# Main.net
KiCad netlist of a schematic drawn in Altium Designer
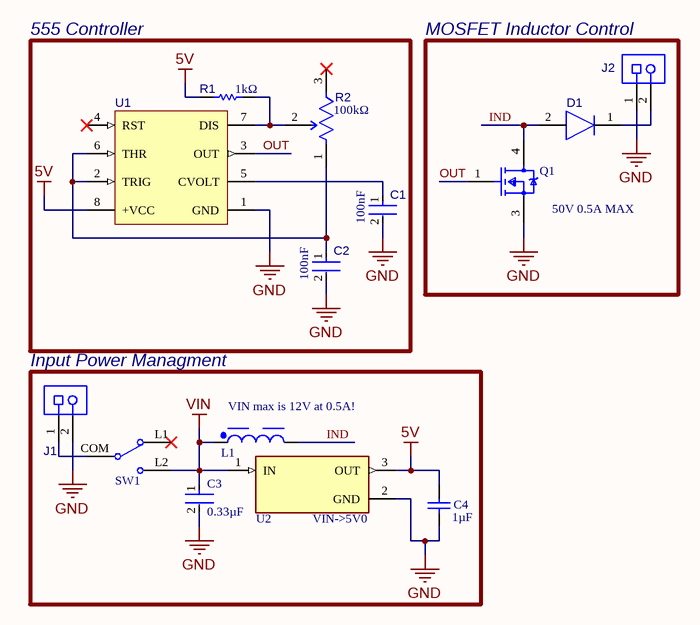
[diagram p0: Main.SchDoc]

(export (version "E")
  (design (tool "Eeschema 10.0.6"))
  (components
    (comp (ref "C1")
      (value "100nF")
      (footprint "FP-1206-L_3_2_0_2-W_1_6_0-MFG")
      (description "General Purpose Ceramic Capacitor, 1206, 100nF, 10%, X7R, 15%, 100V")
      (fields (field (name "TOLERANCE") "10%"))
      (libsource (lib "Altium Content Vault") (part "b4654b650e69147ec39a6b967a45e02"))
    )
    (comp (ref "C2")
      (value "100nF")
      (footprint "FP-1206-L_3_2_0_2-W_1_6_0-MFG")
      (description "General Purpose Ceramic Capacitor, 1206, 100nF, 10%, X7R, 15%, 100V")
      (fields (field (name "TOLERANCE") "10%"))
      (libsource (lib "Altium Content Vault") (part "b4654b650e69147ec39a6b967a45e02"))
    )
    (comp (ref "C3")
      (value "0.33µF")
      (footprint "FP-C1206C-EB-MFG")
      (description "CAP CER 0.33UF 50V X7R 1206")
      (fields
        (field (name "OCTOPART") "https://octopart.com/c1206c334k5ractu-kemet-146059")
        (field (name "MANUFACTURER PART NUMBER") "C1206C334K5RACTU")
      )
      (libsource (lib "Altium Content Vault") (part "b4654b650e69147ec39a6b967a45e02"))
    )
    (comp (ref "C4")
      (value "1µF")
      (footprint "CAPC3216X110X50LL20T25")
      (description "Chip Capacitor, 1 uF, +/- 10%, 50 V, -55 to 125 degC, 1206 (3216 Metric), RoHS, Tape and Reel")
      (fields (field (name "MANUFACTURER") "Kemet") (field (name "TOLERANCE") "10%"))
      (libsource (lib "Altium Content Vault") (part "CAP-NP-2"))
    )
    (comp (ref "D1")
      (value "S1B-13-F")
      (footprint "FP-SMA-MFG")
      (description "DIODE GEN PURP 100V 1A SMA")
      (libsource (lib "Altium Content Vault") (part "03cb15f8d8994b06d21941eb207504f"))
    )
    (comp (ref "J1")
      (value "1729128")
      (footprint "PHOE-1729128-2_V")
      (description "PCB Terminal Block, 13.5 A, 400 V, 2-Pin THD, RoHS, Bulk")
      (fields (field (name "MANUFACTURER") "Phoenix Contact"))
      (libsource (lib "Altium Content Vault") (part "CN-2P-F-R2"))
    )
    (comp (ref "J2")
      (value "1729128")
      (footprint "PHOE-1729128-2_V")
      (description "PCB Terminal Block, 13.5 A, 400 V, 2-Pin THD, RoHS, Bulk")
      (fields (field (name "MANUFACTURER") "Phoenix Contact"))
      (libsource (lib "Altium Content Vault") (part "CN-2P-F-R2"))
    )
    (comp (ref "L1")
      (value "4.7uH")
      (footprint "WE-PDA_7345")
      (description "WE-PDA SMT Shielded Power Inductor, size 7345, 4.7uH, 2.35A, 84mOhm")
      (fields
        (field (name "MANUFACTURER PART NUMBER") "784777047")
        (field (name "MANUFACTURER") "Wurth Elektronik")
      )
      (libsource (lib "Altium_WE-PDA_rev23a") (part "784777047"))
    )
    (comp (ref "Q1")
      (value "IRLZ44NSTRLPBF")
      (footprint "FP-PG-TO263-3-MFG")
      (description "MOSFET N-CH 55V 47A D2PAK")
      (libsource (lib "Altium Content Vault") (part "cdf1c68f84cb049e5ebc85739c3fcf6"))
    )
    (comp (ref "R1")
      (value "1kΩ")
      (footprint "RESC3116X65X50LL20T20")
      (fields (field (name "PART NUMBER") "CRCW12061K00JNEAHP") (field (name "MANUFACTURER") "Vishay Dale"))
      (libsource (lib "Altium Content Vault") (part "RES"))
    )
    (comp (ref "R2")
      (value "100kΩ")
      (footprint "FP-3362P-T-MFG")
      (description "TRIMMER 100K OHM 0.5W PC PIN TOP")
      (fields (field (name "TOLERANCE") "10%"))
      (libsource (lib "Altium Content Vault") (part "13357d81287629c2fd191d242cfa50c"))
    )
    (comp (ref "SW1")
      (value "450301014042")
      (footprint "450301014042")
      (description "WS-SLTV THT Mini Slide Switch, Opposite Side Connection, SPDT, 12VDC, 500mA, 800g")
      (fields (field (name "MANUFACTURER") "Wurth Elektronik"))
      (libsource (lib "Altium_WS-SLTV_rev22a") (part "450301014042"))
    )
    (comp (ref "U1")
      (value "555 Timer IC")
      (footprint "D0008A_M")
      (description "Timer, 8-pin Narrow SOIC, Pb-Free")
      (fields (field (name "MANUFACTURER") "Texas Instruments"))
      (libsource (lib "Altium Content Vault") (part "AN-TIMER-LM555-8"))
    )
    (comp (ref "U2")
      (value "VIN->5V0")
      (footprint "DPAK229P990X238-4N")
      (description "Linear Voltage Regulator IC 1 Output 1A DPAK")
      (fields (field (name "MP") "MC7805BDTRKG") (field (name "MF") "ON Semiconductor"))
      (libsource (lib "MC7805BDTRKG") (part "MC7805BDTRKG"))
    )
  )
  (nets
    (net (code "1") (name "/IND") (class "Default")
      (node (ref "D1") (pin "2") (pinfunction "A_2") (pintype "passive"))
      (node (ref "L1") (pin "2") (pinfunction "2_2") (pintype "passive"))
      (node (ref "Q1") (pin "4") (pinfunction "D_4") (pintype "passive"))
    )
    (net (code "2") (name "/OUT") (class "Default")
      (node (ref "Q1") (pin "1") (pinfunction "G_1") (pintype "passive"))
      (node (ref "U1") (pin "3") (pinfunction "OUT_3") (pintype "output"))
    )
    (net (code "3") (name "5V") (class "Default")
      (node (ref "C4") (pin "1") (pinfunction "1_1") (pintype "passive"))
      (node (ref "R1") (pin "2") (pinfunction "2_2") (pintype "passive"))
      (node (ref "U1") (pin "8") (pinfunction "+VCC_8") (pintype "power_in"))
      (node (ref "U2") (pin "3") (pinfunction "OUT_3") (pintype "output"))
    )
    (net (code "4") (name "GND") (class "Default")
      (node (ref "C1") (pin "2") (pinfunction "2_2") (pintype "passive"))
      (node (ref "C2") (pin "2") (pinfunction "2_2") (pintype "passive"))
      (node (ref "C3") (pin "2") (pinfunction "2_2") (pintype "passive"))
      (node (ref "C4") (pin "2") (pinfunction "2_2") (pintype "passive"))
      (node (ref "J1") (pin "2") (pinfunction "2_2") (pintype "passive"))
      (node (ref "J2") (pin "1") (pinfunction "1_1") (pintype "passive"))
      (node (ref "Q1") (pin "3") (pinfunction "S_3") (pintype "passive"))
      (node (ref "U1") (pin "1") (pinfunction "GND_1") (pintype "power_in"))
      (node (ref "U2") (pin "2") (pinfunction "GND_2") (pintype "power_in"))
    )
    (net (code "5") (name "Net-(D1-C)") (class "Default")
      (node (ref "D1") (pin "1") (pinfunction "C_1") (pintype "passive"))
      (node (ref "J2") (pin "2") (pinfunction "2_2") (pintype "passive"))
    )
    (net (code "6") (name "Net-(J1-Pad1)") (class "Default")
      (node (ref "J1") (pin "1") (pinfunction "1_1") (pintype "passive"))
      (node (ref "SW1") (pin "COM") (pinfunction "COM_COM") (pintype "passive"))
    )
    (net (code "7") (name "Net-(R2-CCW)") (class "Default")
      (node (ref "C2") (pin "1") (pinfunction "1_1") (pintype "passive"))
      (node (ref "R2") (pin "1") (pinfunction "CCW_1") (pintype "passive"))
      (node (ref "U1") (pin "2") (pinfunction "TRIG_2") (pintype "input"))
      (node (ref "U1") (pin "6") (pinfunction "THR_6") (pintype "input"))
    )
    (net (code "8") (name "Net-(R2-WIPER)") (class "Default")
      (node (ref "R1") (pin "1") (pinfunction "1_1") (pintype "passive"))
      (node (ref "R2") (pin "2") (pinfunction "WIPER_2") (pintype "passive"))
      (node (ref "U1") (pin "7") (pinfunction "DIS_7") (pintype "open_collector"))
    )
    (net (code "9") (name "Net-(U1-CVOLT)") (class "Default")
      (node (ref "C1") (pin "1") (pinfunction "1_1") (pintype "passive"))
      (node (ref "U1") (pin "5") (pinfunction "CVOLT_5") (pintype "passive"))
    )
    (net (code "10") (name "VIN") (class "Default")
      (node (ref "C3") (pin "1") (pinfunction "1_1") (pintype "passive"))
      (node (ref "L1") (pin "1") (pinfunction "1_1") (pintype "passive"))
      (node (ref "SW1") (pin "L2") (pinfunction "L2_L2") (pintype "passive"))
      (node (ref "U2") (pin "1") (pinfunction "IN_1") (pintype "input"))
    )
    (net (code "11") (name "unconnected-(R2-CW-Pad3)") (class "Default")
      (node (ref "R2") (pin "3") (pinfunction "CW_3") (pintype "passive+no_connect"))
    )
    (net (code "12") (name "unconnected-(SW1-PadL1)") (class "Default")
      (node (ref "SW1") (pin "L1") (pinfunction "L1_L1") (pintype "passive+no_connect"))
    )
    (net (code "13") (name "unconnected-(U1-RST-Pad4)") (class "Default")
      (node (ref "U1") (pin "4") (pinfunction "RST_4") (pintype "input+no_connect"))
    )
  )
)
